# Power_Cape.net
KiCad netlist of a schematic drawn in EAGLE
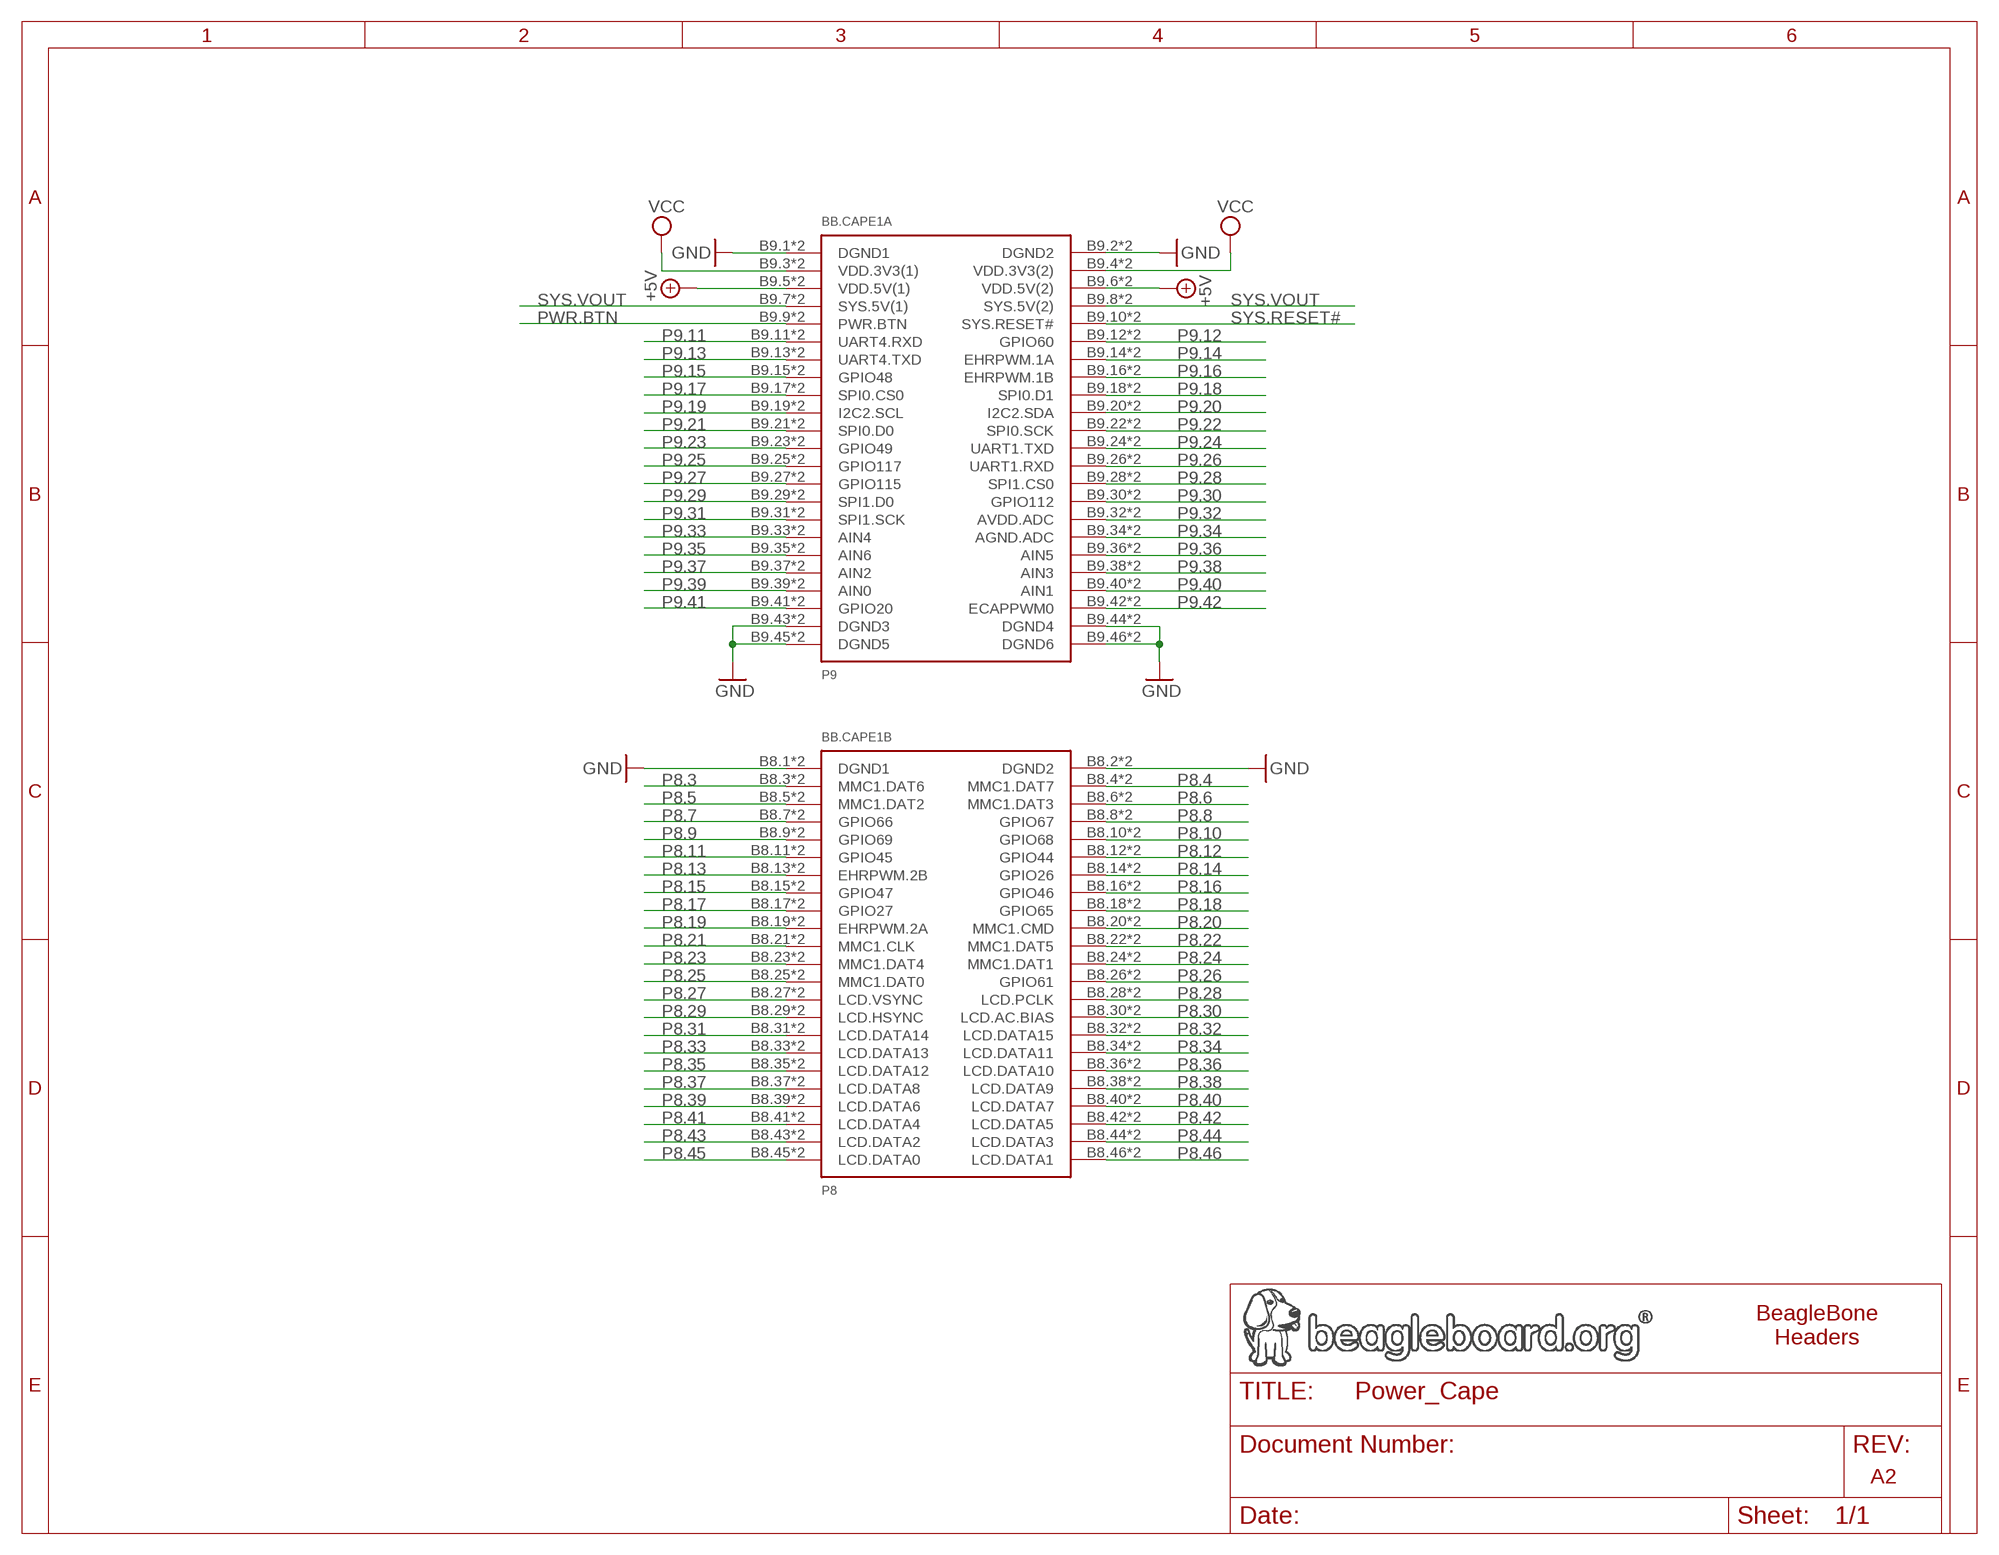
[diagram p0: schematic, sheet 1, part 1 of 2]
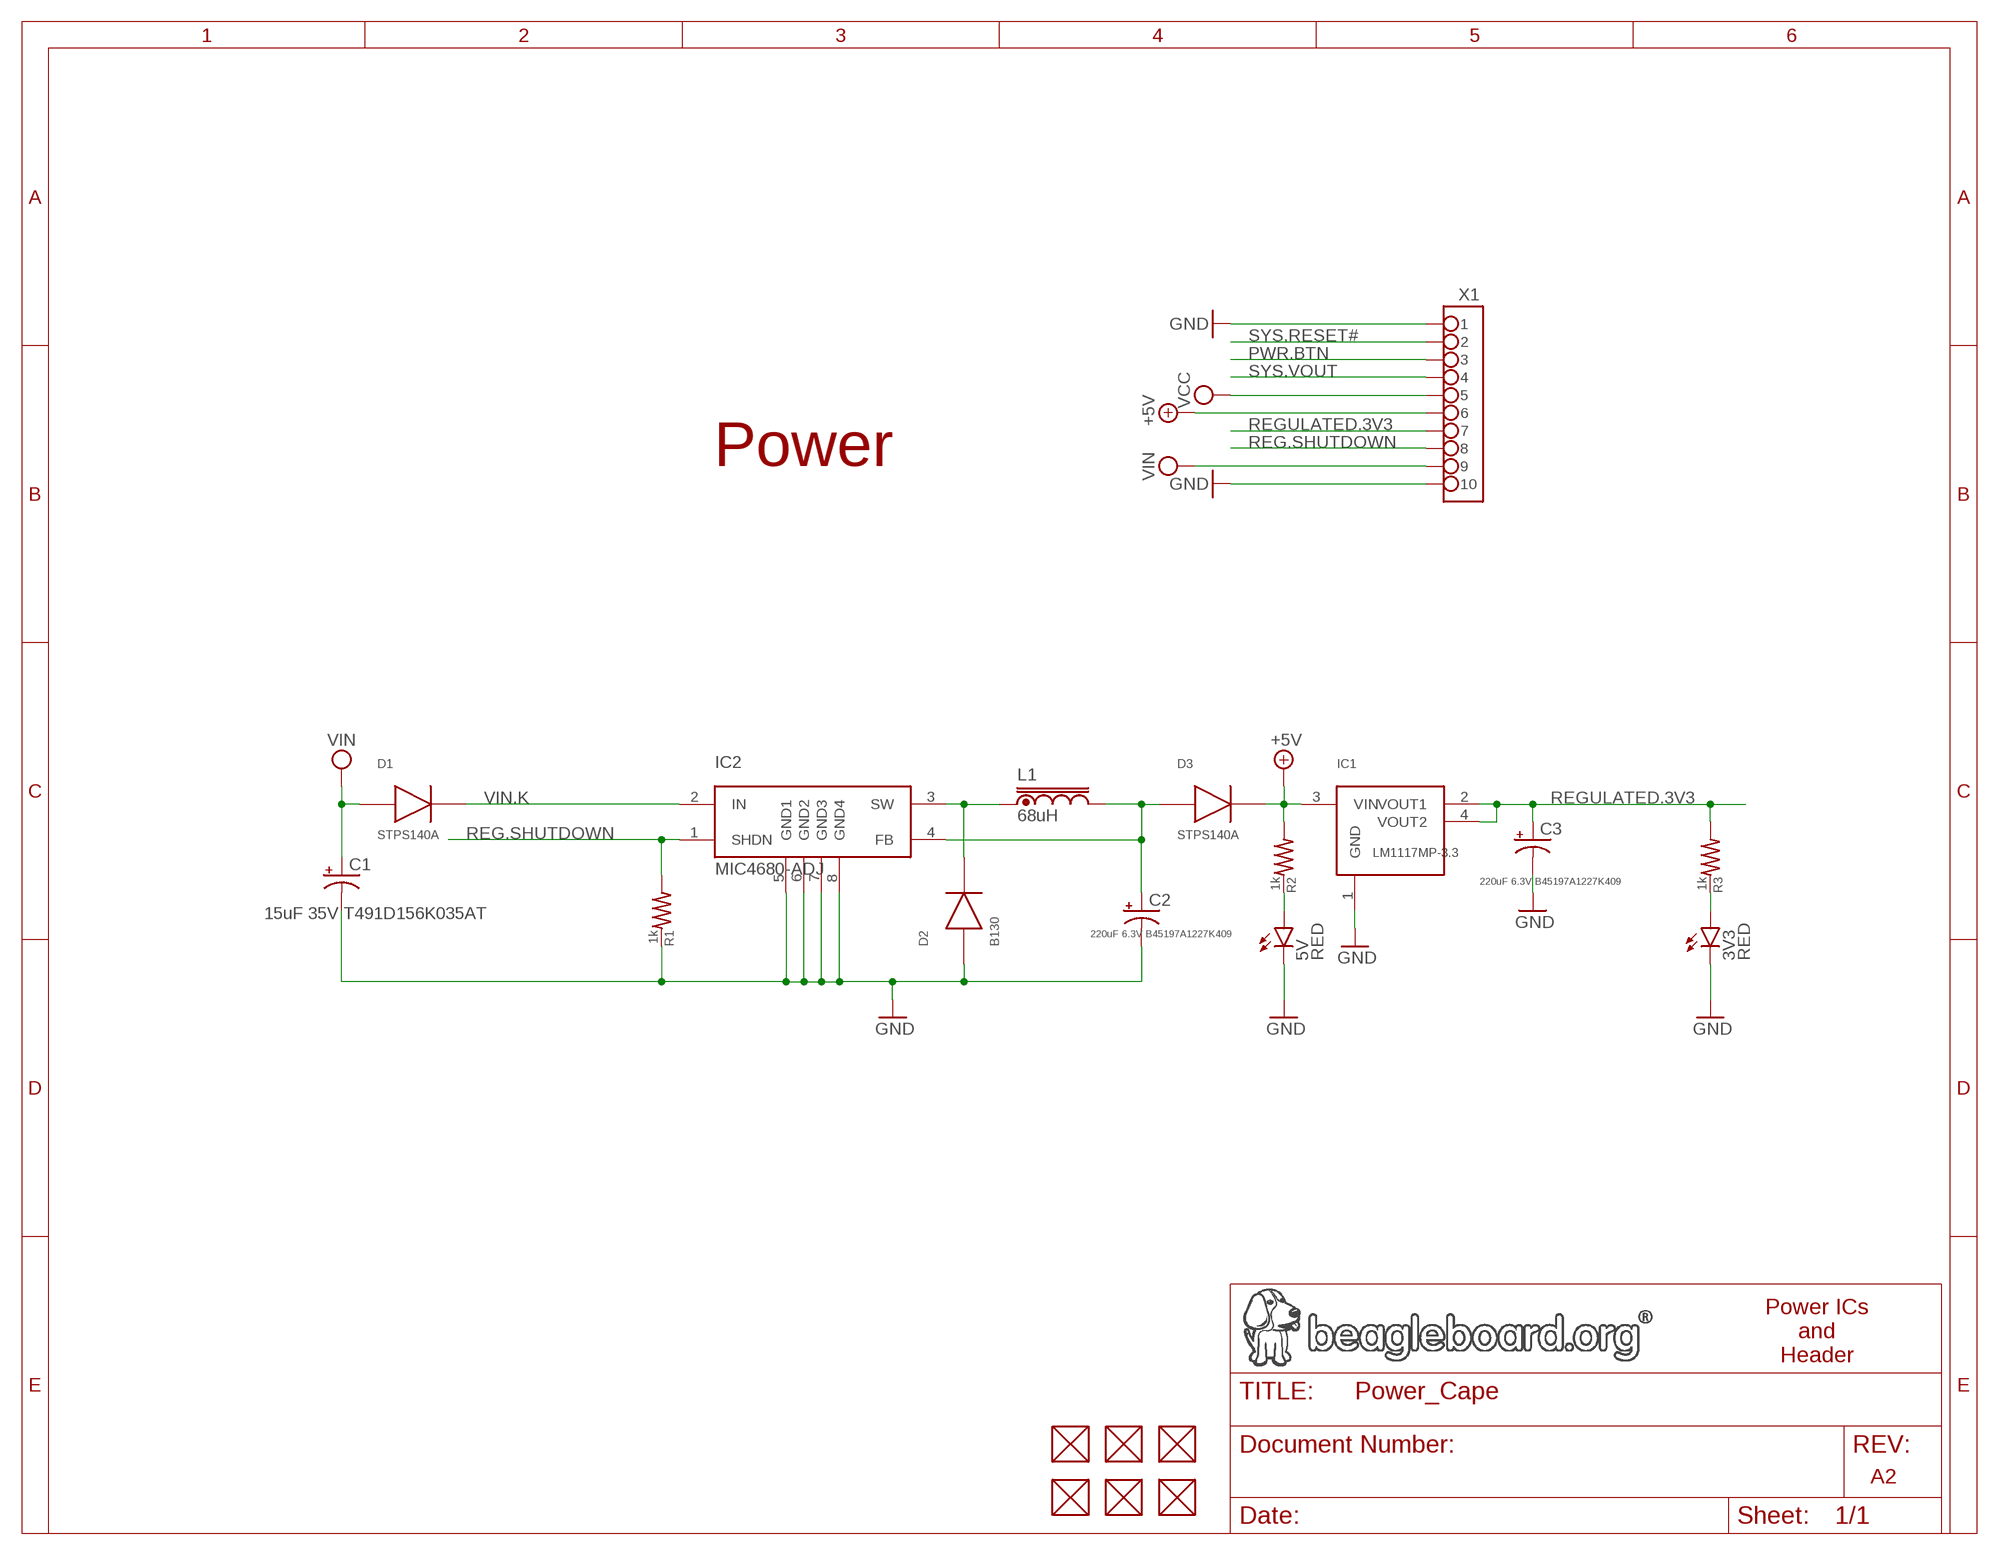
[diagram p1: schematic, sheet 1, part 2 of 2]

(export (version "E")
  (design (tool "Eeschema 10.0.6"))
  (components
    (comp (ref "3V3")
      (value "RED")
      (footprint "eagle-import:0805-LED")
      (libsource (lib "eagle-import") (part "LED-(INCH)-0805"))
    )
    (comp (ref "5V")
      (value "RED")
      (footprint "eagle-import:0805-LED")
      (libsource (lib "eagle-import") (part "LED-(INCH)-0805"))
    )
    (comp (ref "BB.CAPE1")
      (value "BEAGLEBONE.CAPE.TOP/BOTTOM-PADS")
      (footprint "eagle-import:BEAGLEBONE.CAPE.TOP_BOTTOM-PADS")
      (libsource (lib "eagle-import") (part "BEAGLEBONE.CAPE.TOP/BOTTOM-PADS"))
    )
    (comp (ref "C1")
      (value "15uF 35V T491D156K035AT")
      (footprint "eagle-import:D_7343-31W")
      (libsource (lib "eagle-import") (part "CPOL-USD/7343-31W"))
    )
    (comp (ref "C2")
      (value "220uF 6.3V B45197A1227K409")
      (footprint "eagle-import:D_7343-31W")
      (libsource (lib "eagle-import") (part "CPOL-USD/7343-31W"))
    )
    (comp (ref "C3")
      (value "220uF 6.3V B45197A1227K409")
      (footprint "eagle-import:D_7343-31W")
      (libsource (lib "eagle-import") (part "CPOL-USD/7343-31W"))
    )
    (comp (ref "D1")
      (value "STPS140A")
      (footprint "eagle-import:DIODE_SMA")
      (libsource (lib "eagle-import") (part "DIODE_SMA"))
    )
    (comp (ref "D2")
      (value "B130")
      (footprint "eagle-import:DIODE_SMA")
      (libsource (lib "eagle-import") (part "DIODE_SMA"))
    )
    (comp (ref "D3")
      (value "STPS140A")
      (footprint "eagle-import:DIODE_SMA")
      (libsource (lib "eagle-import") (part "DIODE_SMA"))
    )
    (comp (ref "FUD1")
      (value "FIDUCIAL")
      (footprint "eagle-import:FIDUCIAL_40MIL")
      (libsource (lib "eagle-import") (part "FIDUCIAL"))
    )
    (comp (ref "FUD2")
      (value "FIDUCIAL")
      (footprint "eagle-import:FIDUCIAL_40MIL")
      (libsource (lib "eagle-import") (part "FIDUCIAL"))
    )
    (comp (ref "FUD3")
      (value "FIDUCIAL")
      (footprint "eagle-import:FIDUCIAL_40MIL")
      (libsource (lib "eagle-import") (part "FIDUCIAL"))
    )
    (comp (ref "FUD4")
      (value "FIDUCIAL")
      (footprint "eagle-import:FIDUCIAL_40MIL")
      (libsource (lib "eagle-import") (part "FIDUCIAL"))
    )
    (comp (ref "FUD5")
      (value "FIDUCIAL")
      (footprint "eagle-import:FIDUCIAL_40MIL")
      (libsource (lib "eagle-import") (part "FIDUCIAL"))
    )
    (comp (ref "FUD6")
      (value "FIDUCIAL")
      (footprint "eagle-import:FIDUCIAL_40MIL")
      (libsource (lib "eagle-import") (part "FIDUCIAL"))
    )
    (comp (ref "IC1")
      (value "LM1117MP-3.3")
      (footprint "eagle-import:SOT223")
      (libsource (lib "eagle-import") (part "LM1117"))
    )
    (comp (ref "IC2")
      (value "MIC4680-ADJ")
      (footprint "eagle-import:SO8")
      (libsource (lib "eagle-import") (part "MIC4680"))
    )
    (comp (ref "L1")
      (value "68uH")
      (footprint "eagle-import:UP2B-(UNI-PAC)")
      (libsource (lib "eagle-import") (part "UP2B-XXX"))
    )
    (comp (ref "R1")
      (value "1k")
      (footprint "eagle-import:0402")
      (libsource (lib "eagle-import") (part "RESISTOR-(INCH)-0402"))
    )
    (comp (ref "R2")
      (value "1k")
      (footprint "eagle-import:0402")
      (libsource (lib "eagle-import") (part "RESISTOR-(INCH)-0402"))
    )
    (comp (ref "R3")
      (value "1k")
      (footprint "eagle-import:0402")
      (libsource (lib "eagle-import") (part "RESISTOR-(INCH)-0402"))
    )
    (comp (ref "X1")
      (value "TB-10TERM-150MIL.PITCH")
      (footprint "eagle-import:TERMINAL.BLOCK-10TERM-150MIL.PITCH")
      (libsource (lib "eagle-import") (part "TB-10TERM-150MIL.PITCH"))
    )
  )
  (nets
    (net (code "1") (name "+5V") (class "Default")
      (node (ref "BB.CAPE1") (pin "B9.5") (pinfunction "VDD.5V(1)_B9.5") (pintype "bidirectional"))
      (node (ref "BB.CAPE1") (pin "B9.6") (pinfunction "VDD.5V(2)_B9.6") (pintype "bidirectional"))
      (node (ref "BB.CAPE1") (pin "T9.5") (pinfunction "VDD.5V(1)_T9.5") (pintype "bidirectional"))
      (node (ref "BB.CAPE1") (pin "T9.6") (pinfunction "VDD.5V(2)_T9.6") (pintype "bidirectional"))
      (node (ref "D3") (pin "K") (pinfunction "K_K") (pintype "bidirectional"))
      (node (ref "IC1") (pin "3") (pinfunction "VIN_3") (pintype "bidirectional"))
      (node (ref "R2") (pin "1") (pinfunction "1_1") (pintype "bidirectional"))
      (node (ref "X1") (pin "6") (pinfunction "6_6") (pintype "bidirectional"))
    )
    (net (code "2") (name "/P8.3") (class "Default")
      (node (ref "BB.CAPE1") (pin "B8.3") (pinfunction "MMC1.DAT6_B8.3") (pintype "bidirectional"))
      (node (ref "BB.CAPE1") (pin "T8.3") (pinfunction "MMC1.DAT6_T8.3") (pintype "bidirectional"))
    )
    (net (code "3") (name "/P8.4") (class "Default")
      (node (ref "BB.CAPE1") (pin "B8.4") (pinfunction "MMC1.DAT7_B8.4") (pintype "bidirectional"))
      (node (ref "BB.CAPE1") (pin "T8.4") (pinfunction "MMC1.DAT7_T8.4") (pintype "bidirectional"))
    )
    (net (code "4") (name "/P8.5") (class "Default")
      (node (ref "BB.CAPE1") (pin "B8.5") (pinfunction "MMC1.DAT2_B8.5") (pintype "bidirectional"))
      (node (ref "BB.CAPE1") (pin "T8.5") (pinfunction "MMC1.DAT2_T8.5") (pintype "bidirectional"))
    )
    (net (code "5") (name "/P8.6") (class "Default")
      (node (ref "BB.CAPE1") (pin "B8.6") (pinfunction "MMC1.DAT3_B8.6") (pintype "bidirectional"))
      (node (ref "BB.CAPE1") (pin "T8.6") (pinfunction "MMC1.DAT3_T8.6") (pintype "bidirectional"))
    )
    (net (code "6") (name "/P8.7") (class "Default")
      (node (ref "BB.CAPE1") (pin "B8.7") (pinfunction "GPIO66_B8.7") (pintype "bidirectional"))
      (node (ref "BB.CAPE1") (pin "T8.7") (pinfunction "GPIO66_T8.7") (pintype "bidirectional"))
    )
    (net (code "7") (name "/P8.8") (class "Default")
      (node (ref "BB.CAPE1") (pin "B8.8") (pinfunction "GPIO67_B8.8") (pintype "bidirectional"))
      (node (ref "BB.CAPE1") (pin "T8.8") (pinfunction "GPIO67_T8.8") (pintype "bidirectional"))
    )
    (net (code "8") (name "/P8.9") (class "Default")
      (node (ref "BB.CAPE1") (pin "B8.9") (pinfunction "GPIO69_B8.9") (pintype "bidirectional"))
      (node (ref "BB.CAPE1") (pin "T8.9") (pinfunction "GPIO69_T8.9") (pintype "bidirectional"))
    )
    (net (code "9") (name "/P8.10") (class "Default")
      (node (ref "BB.CAPE1") (pin "B8.10") (pinfunction "GPIO68_B8.10") (pintype "bidirectional"))
      (node (ref "BB.CAPE1") (pin "T8.10") (pinfunction "GPIO68_T8.10") (pintype "bidirectional"))
    )
    (net (code "10") (name "/P8.11") (class "Default")
      (node (ref "BB.CAPE1") (pin "B8.11") (pinfunction "GPIO45_B8.11") (pintype "bidirectional"))
      (node (ref "BB.CAPE1") (pin "T8.11") (pinfunction "GPIO45_T8.11") (pintype "bidirectional"))
    )
    (net (code "11") (name "/P8.12") (class "Default")
      (node (ref "BB.CAPE1") (pin "B8.12") (pinfunction "GPIO44_B8.12") (pintype "bidirectional"))
      (node (ref "BB.CAPE1") (pin "T8.12") (pinfunction "GPIO44_T8.12") (pintype "bidirectional"))
    )
    (net (code "12") (name "/P8.13") (class "Default")
      (node (ref "BB.CAPE1") (pin "B8.13") (pinfunction "EHRPWM.2B_B8.13") (pintype "bidirectional"))
      (node (ref "BB.CAPE1") (pin "T8.13") (pinfunction "EHRPWM.2B_T8.13") (pintype "bidirectional"))
    )
    (net (code "13") (name "/P8.14") (class "Default")
      (node (ref "BB.CAPE1") (pin "B8.14") (pinfunction "GPIO26_B8.14") (pintype "bidirectional"))
      (node (ref "BB.CAPE1") (pin "T8.14") (pinfunction "GPIO26_T8.14") (pintype "bidirectional"))
    )
    (net (code "14") (name "/P8.15") (class "Default")
      (node (ref "BB.CAPE1") (pin "B8.15") (pinfunction "GPIO47_B8.15") (pintype "bidirectional"))
      (node (ref "BB.CAPE1") (pin "T8.15") (pinfunction "GPIO47_T8.15") (pintype "bidirectional"))
    )
    (net (code "15") (name "/P8.16") (class "Default")
      (node (ref "BB.CAPE1") (pin "B8.16") (pinfunction "GPIO46_B8.16") (pintype "bidirectional"))
      (node (ref "BB.CAPE1") (pin "T8.16") (pinfunction "GPIO46_T8.16") (pintype "bidirectional"))
    )
    (net (code "16") (name "/P8.17") (class "Default")
      (node (ref "BB.CAPE1") (pin "B8.17") (pinfunction "GPIO27_B8.17") (pintype "bidirectional"))
      (node (ref "BB.CAPE1") (pin "T8.17") (pinfunction "GPIO27_T8.17") (pintype "bidirectional"))
    )
    (net (code "17") (name "/P8.18") (class "Default")
      (node (ref "BB.CAPE1") (pin "B8.18") (pinfunction "GPIO65_B8.18") (pintype "bidirectional"))
      (node (ref "BB.CAPE1") (pin "T8.18") (pinfunction "GPIO65_T8.18") (pintype "bidirectional"))
    )
    (net (code "18") (name "/P8.19") (class "Default")
      (node (ref "BB.CAPE1") (pin "B8.19") (pinfunction "EHRPWM.2A_B8.19") (pintype "bidirectional"))
      (node (ref "BB.CAPE1") (pin "T8.19") (pinfunction "EHRPWM.2A_T8.19") (pintype "bidirectional"))
    )
    (net (code "19") (name "/P8.20") (class "Default")
      (node (ref "BB.CAPE1") (pin "B8.20") (pinfunction "MMC1.CMD_B8.20") (pintype "bidirectional"))
      (node (ref "BB.CAPE1") (pin "T8.20") (pinfunction "MMC1.CMD_T8.20") (pintype "bidirectional"))
    )
    (net (code "20") (name "/P8.21") (class "Default")
      (node (ref "BB.CAPE1") (pin "B8.21") (pinfunction "MMC1.CLK_B8.21") (pintype "bidirectional"))
      (node (ref "BB.CAPE1") (pin "T8.21") (pinfunction "MMC1.CLK_T8.21") (pintype "bidirectional"))
    )
    (net (code "21") (name "/P8.22") (class "Default")
      (node (ref "BB.CAPE1") (pin "B8.22") (pinfunction "MMC1.DAT5_B8.22") (pintype "bidirectional"))
      (node (ref "BB.CAPE1") (pin "T8.22") (pinfunction "MMC1.DAT5_T8.22") (pintype "bidirectional"))
    )
    (net (code "22") (name "/P8.23") (class "Default")
      (node (ref "BB.CAPE1") (pin "B8.23") (pinfunction "MMC1.DAT4_B8.23") (pintype "bidirectional"))
      (node (ref "BB.CAPE1") (pin "T8.23") (pinfunction "MMC1.DAT4_T8.23") (pintype "bidirectional"))
    )
    (net (code "23") (name "/P8.24") (class "Default")
      (node (ref "BB.CAPE1") (pin "B8.24") (pinfunction "MMC1.DAT1_B8.24") (pintype "bidirectional"))
      (node (ref "BB.CAPE1") (pin "T8.24") (pinfunction "MMC1.DAT1_T8.24") (pintype "bidirectional"))
    )
    (net (code "24") (name "/P8.25") (class "Default")
      (node (ref "BB.CAPE1") (pin "B8.25") (pinfunction "MMC1.DAT0_B8.25") (pintype "bidirectional"))
      (node (ref "BB.CAPE1") (pin "T8.25") (pinfunction "MMC1.DAT0_T8.25") (pintype "bidirectional"))
    )
    (net (code "25") (name "/P8.26") (class "Default")
      (node (ref "BB.CAPE1") (pin "B8.26") (pinfunction "GPIO61_B8.26") (pintype "bidirectional"))
      (node (ref "BB.CAPE1") (pin "T8.26") (pinfunction "GPIO61_T8.26") (pintype "bidirectional"))
    )
    (net (code "26") (name "/P8.27") (class "Default")
      (node (ref "BB.CAPE1") (pin "B8.27") (pinfunction "LCD.VSYNC_B8.27") (pintype "bidirectional"))
      (node (ref "BB.CAPE1") (pin "T8.27") (pinfunction "LCD.VSYNC_T8.27") (pintype "bidirectional"))
    )
    (net (code "27") (name "/P8.28") (class "Default")
      (node (ref "BB.CAPE1") (pin "B8.28") (pinfunction "LCD.PCLK_B8.28") (pintype "bidirectional"))
      (node (ref "BB.CAPE1") (pin "T8.28") (pinfunction "LCD.PCLK_T8.28") (pintype "bidirectional"))
    )
    (net (code "28") (name "/P8.29") (class "Default")
      (node (ref "BB.CAPE1") (pin "B8.29") (pinfunction "LCD.HSYNC_B8.29") (pintype "bidirectional"))
      (node (ref "BB.CAPE1") (pin "T8.29") (pinfunction "LCD.HSYNC_T8.29") (pintype "bidirectional"))
    )
    (net (code "29") (name "/P8.30") (class "Default")
      (node (ref "BB.CAPE1") (pin "B8.30") (pinfunction "LCD.AC.BIAS_B8.30") (pintype "bidirectional"))
      (node (ref "BB.CAPE1") (pin "T8.30") (pinfunction "LCD.AC.BIAS_T8.30") (pintype "bidirectional"))
    )
    (net (code "30") (name "/P8.31") (class "Default")
      (node (ref "BB.CAPE1") (pin "B8.31") (pinfunction "LCD.DATA14_B8.31") (pintype "bidirectional"))
      (node (ref "BB.CAPE1") (pin "T8.31") (pinfunction "LCD.DATA14_T8.31") (pintype "bidirectional"))
    )
    (net (code "31") (name "/P8.32") (class "Default")
      (node (ref "BB.CAPE1") (pin "B8.32") (pinfunction "LCD.DATA15_B8.32") (pintype "bidirectional"))
      (node (ref "BB.CAPE1") (pin "T8.32") (pinfunction "LCD.DATA15_T8.32") (pintype "bidirectional"))
    )
    (net (code "32") (name "/P8.33") (class "Default")
      (node (ref "BB.CAPE1") (pin "B8.33") (pinfunction "LCD.DATA13_B8.33") (pintype "bidirectional"))
      (node (ref "BB.CAPE1") (pin "T8.33") (pinfunction "LCD.DATA13_T8.33") (pintype "bidirectional"))
    )
    (net (code "33") (name "/P8.34") (class "Default")
      (node (ref "BB.CAPE1") (pin "B8.34") (pinfunction "LCD.DATA11_B8.34") (pintype "bidirectional"))
      (node (ref "BB.CAPE1") (pin "T8.34") (pinfunction "LCD.DATA11_T8.34") (pintype "bidirectional"))
    )
    (net (code "34") (name "/P8.35") (class "Default")
      (node (ref "BB.CAPE1") (pin "B8.35") (pinfunction "LCD.DATA12_B8.35") (pintype "bidirectional"))
      (node (ref "BB.CAPE1") (pin "T8.35") (pinfunction "LCD.DATA12_T8.35") (pintype "bidirectional"))
    )
    (net (code "35") (name "/P8.36") (class "Default")
      (node (ref "BB.CAPE1") (pin "B8.36") (pinfunction "LCD.DATA10_B8.36") (pintype "bidirectional"))
      (node (ref "BB.CAPE1") (pin "T8.36") (pinfunction "LCD.DATA10_T8.36") (pintype "bidirectional"))
    )
    (net (code "36") (name "/P8.37") (class "Default")
      (node (ref "BB.CAPE1") (pin "B8.37") (pinfunction "LCD.DATA8_B8.37") (pintype "bidirectional"))
      (node (ref "BB.CAPE1") (pin "T8.37") (pinfunction "LCD.DATA8_T8.37") (pintype "bidirectional"))
    )
    (net (code "37") (name "/P8.38") (class "Default")
      (node (ref "BB.CAPE1") (pin "B8.38") (pinfunction "LCD.DATA9_B8.38") (pintype "bidirectional"))
      (node (ref "BB.CAPE1") (pin "T8.38") (pinfunction "LCD.DATA9_T8.38") (pintype "bidirectional"))
    )
    (net (code "38") (name "/P8.39") (class "Default")
      (node (ref "BB.CAPE1") (pin "B8.39") (pinfunction "LCD.DATA6_B8.39") (pintype "bidirectional"))
      (node (ref "BB.CAPE1") (pin "T8.39") (pinfunction "LCD.DATA6_T8.39") (pintype "bidirectional"))
    )
    (net (code "39") (name "/P8.40") (class "Default")
      (node (ref "BB.CAPE1") (pin "B8.40") (pinfunction "LCD.DATA7_B8.40") (pintype "bidirectional"))
      (node (ref "BB.CAPE1") (pin "T8.40") (pinfunction "LCD.DATA7_T8.40") (pintype "bidirectional"))
    )
    (net (code "40") (name "/P8.41") (class "Default")
      (node (ref "BB.CAPE1") (pin "B8.41") (pinfunction "LCD.DATA4_B8.41") (pintype "bidirectional"))
      (node (ref "BB.CAPE1") (pin "T8.41") (pinfunction "LCD.DATA4_T8.41") (pintype "bidirectional"))
    )
    (net (code "41") (name "/P8.42") (class "Default")
      (node (ref "BB.CAPE1") (pin "B8.42") (pinfunction "LCD.DATA5_B8.42") (pintype "bidirectional"))
      (node (ref "BB.CAPE1") (pin "T8.42") (pinfunction "LCD.DATA5_T8.42") (pintype "bidirectional"))
    )
    (net (code "42") (name "/P8.43") (class "Default")
      (node (ref "BB.CAPE1") (pin "B8.43") (pinfunction "LCD.DATA2_B8.43") (pintype "bidirectional"))
      (node (ref "BB.CAPE1") (pin "T8.43") (pinfunction "LCD.DATA2_T8.43") (pintype "bidirectional"))
    )
    (net (code "43") (name "/P8.44") (class "Default")
      (node (ref "BB.CAPE1") (pin "B8.44") (pinfunction "LCD.DATA3_B8.44") (pintype "bidirectional"))
      (node (ref "BB.CAPE1") (pin "T8.44") (pinfunction "LCD.DATA3_T8.44") (pintype "bidirectional"))
    )
    (net (code "44") (name "/P8.45") (class "Default")
      (node (ref "BB.CAPE1") (pin "B8.45") (pinfunction "LCD.DATA0_B8.45") (pintype "bidirectional"))
      (node (ref "BB.CAPE1") (pin "T8.45") (pinfunction "LCD.DATA0_T8.45") (pintype "bidirectional"))
    )
    (net (code "45") (name "/P8.46") (class "Default")
      (node (ref "BB.CAPE1") (pin "B8.46") (pinfunction "LCD.DATA1_B8.46") (pintype "bidirectional"))
      (node (ref "BB.CAPE1") (pin "T8.46") (pinfunction "LCD.DATA1_T8.46") (pintype "bidirectional"))
    )
    (net (code "46") (name "/P9.11") (class "Default")
      (node (ref "BB.CAPE1") (pin "B9.11") (pinfunction "UART4.RXD_B9.11") (pintype "bidirectional"))
      (node (ref "BB.CAPE1") (pin "T9.11") (pinfunction "UART4.RXD_T9.11") (pintype "bidirectional"))
    )
    (net (code "47") (name "/P9.12") (class "Default")
      (node (ref "BB.CAPE1") (pin "B9.12") (pinfunction "GPIO60_B9.12") (pintype "bidirectional"))
      (node (ref "BB.CAPE1") (pin "T9.12") (pinfunction "GPIO60_T9.12") (pintype "bidirectional"))
    )
    (net (code "48") (name "/P9.13") (class "Default")
      (node (ref "BB.CAPE1") (pin "B9.13") (pinfunction "UART4.TXD_B9.13") (pintype "bidirectional"))
      (node (ref "BB.CAPE1") (pin "T9.13") (pinfunction "UART4.TXD_T9.13") (pintype "bidirectional"))
    )
    (net (code "49") (name "/P9.14") (class "Default")
      (node (ref "BB.CAPE1") (pin "B9.14") (pinfunction "EHRPWM.1A_B9.14") (pintype "bidirectional"))
      (node (ref "BB.CAPE1") (pin "T9.14") (pinfunction "EHRPWM.1A_T9.14") (pintype "bidirectional"))
    )
    (net (code "50") (name "/P9.15") (class "Default")
      (node (ref "BB.CAPE1") (pin "B9.15") (pinfunction "GPIO48_B9.15") (pintype "bidirectional"))
      (node (ref "BB.CAPE1") (pin "T9.15") (pinfunction "GPIO48_T9.15") (pintype "bidirectional"))
    )
    (net (code "51") (name "/P9.16") (class "Default")
      (node (ref "BB.CAPE1") (pin "B9.16") (pinfunction "EHRPWM.1B_B9.16") (pintype "bidirectional"))
      (node (ref "BB.CAPE1") (pin "T9.16") (pinfunction "EHRPWM.1B_T9.16") (pintype "bidirectional"))
    )
    (net (code "52") (name "/P9.17") (class "Default")
      (node (ref "BB.CAPE1") (pin "B9.17") (pinfunction "SPI0.CS0_B9.17") (pintype "bidirectional"))
      (node (ref "BB.CAPE1") (pin "T9.17") (pinfunction "SPI0.CS0_T9.17") (pintype "bidirectional"))
    )
    (net (code "53") (name "/P9.18") (class "Default")
      (node (ref "BB.CAPE1") (pin "B9.18") (pinfunction "SPI0.D1_B9.18") (pintype "bidirectional"))
      (node (ref "BB.CAPE1") (pin "T9.18") (pinfunction "SPI0.D1_T9.18") (pintype "bidirectional"))
    )
    (net (code "54") (name "/P9.19") (class "Default")
      (node (ref "BB.CAPE1") (pin "B9.19") (pinfunction "I2C2.SCL_B9.19") (pintype "bidirectional"))
      (node (ref "BB.CAPE1") (pin "T9.19") (pinfunction "I2C2.SCL_T9.19") (pintype "bidirectional"))
    )
    (net (code "55") (name "/P9.20") (class "Default")
      (node (ref "BB.CAPE1") (pin "B9.20") (pinfunction "I2C2.SDA_B9.20") (pintype "bidirectional"))
      (node (ref "BB.CAPE1") (pin "T9.20") (pinfunction "I2C2.SDA_T9.20") (pintype "bidirectional"))
    )
    (net (code "56") (name "/P9.21") (class "Default")
      (node (ref "BB.CAPE1") (pin "B9.21") (pinfunction "SPI0.D0_B9.21") (pintype "bidirectional"))
      (node (ref "BB.CAPE1") (pin "T9.21") (pinfunction "SPI0.D0_T9.21") (pintype "bidirectional"))
    )
    (net (code "57") (name "/P9.22") (class "Default")
      (node (ref "BB.CAPE1") (pin "B9.22") (pinfunction "SPI0.SCK_B9.22") (pintype "bidirectional"))
      (node (ref "BB.CAPE1") (pin "T9.22") (pinfunction "SPI0.SCK_T9.22") (pintype "bidirectional"))
    )
    (net (code "58") (name "/P9.23") (class "Default")
      (node (ref "BB.CAPE1") (pin "B9.23") (pinfunction "GPIO49_B9.23") (pintype "bidirectional"))
      (node (ref "BB.CAPE1") (pin "T9.23") (pinfunction "GPIO49_T9.23") (pintype "bidirectional"))
    )
    (net (code "59") (name "/P9.24") (class "Default")
      (node (ref "BB.CAPE1") (pin "B9.24") (pinfunction "UART1.TXD_B9.24") (pintype "bidirectional"))
      (node (ref "BB.CAPE1") (pin "T9.24") (pinfunction "UART1.TXD_T9.24") (pintype "bidirectional"))
    )
    (net (code "60") (name "/P9.25") (class "Default")
      (node (ref "BB.CAPE1") (pin "B9.25") (pinfunction "GPIO117_B9.25") (pintype "bidirectional"))
      (node (ref "BB.CAPE1") (pin "T9.25") (pinfunction "GPIO117_T9.25") (pintype "bidirectional"))
    )
    (net (code "61") (name "/P9.26") (class "Default")
      (node (ref "BB.CAPE1") (pin "B9.26") (pinfunction "UART1.RXD_B9.26") (pintype "bidirectional"))
      (node (ref "BB.CAPE1") (pin "T9.26") (pinfunction "UART1.RXD_T9.26") (pintype "bidirectional"))
    )
    (net (code "62") (name "/P9.27") (class "Default")
      (node (ref "BB.CAPE1") (pin "B9.27") (pinfunction "GPIO115_B9.27") (pintype "bidirectional"))
      (node (ref "BB.CAPE1") (pin "T9.27") (pinfunction "GPIO115_T9.27") (pintype "bidirectional"))
    )
    (net (code "63") (name "/P9.28") (class "Default")
      (node (ref "BB.CAPE1") (pin "B9.28") (pinfunction "SPI1.CS0_B9.28") (pintype "bidirectional"))
      (node (ref "BB.CAPE1") (pin "T9.28") (pinfunction "SPI1.CS0_T9.28") (pintype "bidirectional"))
    )
    (net (code "64") (name "/P9.29") (class "Default")
      (node (ref "BB.CAPE1") (pin "B9.29") (pinfunction "SPI1.D0_B9.29") (pintype "bidirectional"))
      (node (ref "BB.CAPE1") (pin "T9.29") (pinfunction "SPI1.D0_T9.29") (pintype "bidirectional"))
    )
    (net (code "65") (name "/P9.30") (class "Default")
      (node (ref "BB.CAPE1") (pin "B9.30") (pinfunction "GPIO112_B9.30") (pintype "bidirectional"))
      (node (ref "BB.CAPE1") (pin "T9.30") (pinfunction "GPIO112_T9.30") (pintype "bidirectional"))
    )
    (net (code "66") (name "/P9.31") (class "Default")
      (node (ref "BB.CAPE1") (pin "B9.31") (pinfunction "SPI1.SCK_B9.31") (pintype "bidirectional"))
      (node (ref "BB.CAPE1") (pin "T9.31") (pinfunction "SPI1.SCK_T9.31") (pintype "bidirectional"))
    )
    (net (code "67") (name "/P9.32") (class "Default")
      (node (ref "BB.CAPE1") (pin "B9.32") (pinfunction "AVDD.ADC_B9.32") (pintype "bidirectional"))
      (node (ref "BB.CAPE1") (pin "T9.32") (pinfunction "AVDD.ADC_T9.32") (pintype "bidirectional"))
    )
    (net (code "68") (name "/P9.33") (class "Default")
      (node (ref "BB.CAPE1") (pin "B9.33") (pinfunction "AIN4_B9.33") (pintype "bidirectional"))
      (node (ref "BB.CAPE1") (pin "T9.33") (pinfunction "AIN4_T9.33") (pintype "bidirectional"))
    )
    (net (code "69") (name "/P9.34") (class "Default")
      (node (ref "BB.CAPE1") (pin "B9.34") (pinfunction "AGND.ADC_B9.34") (pintype "bidirectional"))
      (node (ref "BB.CAPE1") (pin "T9.34") (pinfunction "AGND.ADC_T9.34") (pintype "bidirectional"))
    )
    (net (code "70") (name "/P9.35") (class "Default")
      (node (ref "BB.CAPE1") (pin "B9.35") (pinfunction "AIN6_B9.35") (pintype "bidirectional"))
      (node (ref "BB.CAPE1") (pin "T9.35") (pinfunction "AIN6_T9.35") (pintype "bidirectional"))
    )
    (net (code "71") (name "/P9.36") (class "Default")
      (node (ref "BB.CAPE1") (pin "B9.36") (pinfunction "AIN5_B9.36") (pintype "bidirectional"))
      (node (ref "BB.CAPE1") (pin "T9.36") (pinfunction "AIN5_T9.36") (pintype "bidirectional"))
    )
    (net (code "72") (name "/P9.37") (class "Default")
      (node (ref "BB.CAPE1") (pin "B9.37") (pinfunction "AIN2_B9.37") (pintype "bidirectional"))
      (node (ref "BB.CAPE1") (pin "T9.37") (pinfunction "AIN2_T9.37") (pintype "bidirectional"))
    )
    (net (code "73") (name "/P9.38") (class "Default")
      (node (ref "BB.CAPE1") (pin "B9.38") (pinfunction "AIN3_B9.38") (pintype "bidirectional"))
      (node (ref "BB.CAPE1") (pin "T9.38") (pinfunction "AIN3_T9.38") (pintype "bidirectional"))
    )
    (net (code "74") (name "/P9.39") (class "Default")
      (node (ref "BB.CAPE1") (pin "B9.39") (pinfunction "AIN0_B9.39") (pintype "bidirectional"))
      (node (ref "BB.CAPE1") (pin "T9.39") (pinfunction "AIN0_T9.39") (pintype "bidirectional"))
    )
    (net (code "75") (name "/P9.40") (class "Default")
      (node (ref "BB.CAPE1") (pin "B9.40") (pinfunction "AIN1_B9.40") (pintype "bidirectional"))
      (node (ref "BB.CAPE1") (pin "T9.40") (pinfunction "AIN1_T9.40") (pintype "bidirectional"))
    )
    (net (code "76") (name "/P9.41") (class "Default")
      (node (ref "BB.CAPE1") (pin "B9.41") (pinfunction "GPIO20_B9.41") (pintype "bidirectional"))
      (node (ref "BB.CAPE1") (pin "T9.41") (pinfunction "GPIO20_T9.41") (pintype "bidirectional"))
    )
    (net (code "77") (name "/P9.42") (class "Default")
      (node (ref "BB.CAPE1") (pin "B9.42") (pinfunction "ECAPPWM0_B9.42") (pintype "bidirectional"))
      (node (ref "BB.CAPE1") (pin "T9.42") (pinfunction "ECAPPWM0_T9.42") (pintype "bidirectional"))
    )
    (net (code "78") (name "/PWR.BTN") (class "Default")
      (node (ref "BB.CAPE1") (pin "B9.9") (pinfunction "PWR.BTN_B9.9") (pintype "bidirectional"))
      (node (ref "BB.CAPE1") (pin "T9.9") (pinfunction "PWR.BTN_T9.9") (pintype "bidirectional"))
      (node (ref "X1") (pin "3") (pinfunction "3_3") (pintype "bidirectional"))
    )
    (net (code "79") (name "/REG.SHUTDOWN") (class "Default")
      (node (ref "IC2") (pin "1") (pinfunction "SHDN_1") (pintype "bidirectional"))
      (node (ref "R1") (pin "1") (pinfunction "1_1") (pintype "bidirectional"))
      (node (ref "X1") (pin "8") (pinfunction "8_8") (pintype "bidirectional"))
    )
    (net (code "80") (name "/REGULATED.3V3") (class "Default")
      (node (ref "C3") (pin "+") (pinfunction "+_+") (pintype "passive"))
      (node (ref "IC1") (pin "2") (pinfunction "VOUT1_2") (pintype "bidirectional"))
      (node (ref "IC1") (pin "4") (pinfunction "VOUT2_4") (pintype "bidirectional"))
      (node (ref "R3") (pin "1") (pinfunction "1_1") (pintype "bidirectional"))
      (node (ref "X1") (pin "7") (pinfunction "7_7") (pintype "bidirectional"))
    )
    (net (code "81") (name "/SYS.RESET#") (class "Default")
      (node (ref "BB.CAPE1") (pin "B9.10") (pinfunction "SYS.RESET#_B9.10") (pintype "bidirectional"))
      (node (ref "BB.CAPE1") (pin "T9.10") (pinfunction "SYS.RESET#_T9.10") (pintype "bidirectional"))
      (node (ref "X1") (pin "2") (pinfunction "2_2") (pintype "bidirectional"))
    )
    (net (code "82") (name "/SYS.VOUT") (class "Default")
      (node (ref "BB.CAPE1") (pin "B9.7") (pinfunction "SYS.5V(1)_B9.7") (pintype "bidirectional"))
      (node (ref "BB.CAPE1") (pin "B9.8") (pinfunction "SYS.5V(2)_B9.8") (pintype "bidirectional"))
      (node (ref "BB.CAPE1") (pin "T9.7") (pinfunction "SYS.5V(1)_T9.7") (pintype "bidirectional"))
      (node (ref "BB.CAPE1") (pin "T9.8") (pinfunction "SYS.5V(2)_T9.8") (pintype "bidirectional"))
      (node (ref "X1") (pin "4") (pinfunction "4_4") (pintype "bidirectional"))
    )
    (net (code "83") (name "/VIN.K") (class "Default")
      (node (ref "D1") (pin "K") (pinfunction "K_K") (pintype "bidirectional"))
      (node (ref "IC2") (pin "2") (pinfunction "IN_2") (pintype "bidirectional"))
    )
    (net (code "84") (name "GND") (class "Default")
      (node (ref "3V3") (pin "K") (pinfunction "K_K") (pintype "passive"))
      (node (ref "5V") (pin "K") (pinfunction "K_K") (pintype "passive"))
      (node (ref "BB.CAPE1") (pin "B8.1") (pinfunction "DGND1_B8.1") (pintype "bidirectional"))
      (node (ref "BB.CAPE1") (pin "B8.2") (pinfunction "DGND2_B8.2") (pintype "bidirectional"))
      (node (ref "BB.CAPE1") (pin "B9.1") (pinfunction "DGND1_B9.1") (pintype "bidirectional"))
      (node (ref "BB.CAPE1") (pin "B9.2") (pinfunction "DGND2_B9.2") (pintype "bidirectional"))
      (node (ref "BB.CAPE1") (pin "B9.43") (pinfunction "DGND3_B9.43") (pintype "bidirectional"))
      (node (ref "BB.CAPE1") (pin "B9.44") (pinfunction "DGND4_B9.44") (pintype "bidirectional"))
      (node (ref "BB.CAPE1") (pin "B9.45") (pinfunction "DGND5_B9.45") (pintype "bidirectional"))
      (node (ref "BB.CAPE1") (pin "B9.46") (pinfunction "DGND6_B9.46") (pintype "bidirectional"))
      (node (ref "BB.CAPE1") (pin "T8.1") (pinfunction "DGND1_T8.1") (pintype "bidirectional"))
      (node (ref "BB.CAPE1") (pin "T8.2") (pinfunction "DGND2_T8.2") (pintype "bidirectional"))
      (node (ref "BB.CAPE1") (pin "T9.1") (pinfunction "DGND1_T9.1") (pintype "bidirectional"))
      (node (ref "BB.CAPE1") (pin "T9.2") (pinfunction "DGND2_T9.2") (pintype "bidirectional"))
      (node (ref "BB.CAPE1") (pin "T9.43") (pinfunction "DGND3_T9.43") (pintype "bidirectional"))
      (node (ref "BB.CAPE1") (pin "T9.44") (pinfunction "DGND4_T9.44") (pintype "bidirectional"))
      (node (ref "BB.CAPE1") (pin "T9.45") (pinfunction "DGND5_T9.45") (pintype "bidirectional"))
      (node (ref "BB.CAPE1") (pin "T9.46") (pinfunction "DGND6_T9.46") (pintype "bidirectional"))
      (node (ref "C1") (pin "-") (pinfunction "-_-") (pintype "passive"))
      (node (ref "C2") (pin "-") (pinfunction "-_-") (pintype "passive"))
      (node (ref "C3") (pin "-") (pinfunction "-_-") (pintype "passive"))
      (node (ref "D2") (pin "A") (pinfunction "A_A") (pintype "bidirectional"))
      (node (ref "IC1") (pin "1") (pinfunction "GND_1") (pintype "bidirectional"))
      (node (ref "IC2") (pin "5") (pinfunction "GND1_5") (pintype "bidirectional"))
      (node (ref "IC2") (pin "6") (pinfunction "GND2_6") (pintype "bidirectional"))
      (node (ref "IC2") (pin "7") (pinfunction "GND3_7") (pintype "bidirectional"))
      (node (ref "IC2") (pin "8") (pinfunction "GND4_8") (pintype "bidirectional"))
      (node (ref "R1") (pin "2") (pinfunction "2_2") (pintype "bidirectional"))
      (node (ref "X1") (pin "1") (pinfunction "1_1") (pintype "bidirectional"))
      (node (ref "X1") (pin "10") (pinfunction "10_10") (pintype "bidirectional"))
    )
    (net (code "85") (name "Net-(3V3-PadA)") (class "Default")
      (node (ref "3V3") (pin "A") (pinfunction "A_A") (pintype "passive"))
      (node (ref "R3") (pin "2") (pinfunction "2_2") (pintype "bidirectional"))
    )
    (net (code "86") (name "Net-(5V-PadA)") (class "Default")
      (node (ref "5V") (pin "A") (pinfunction "A_A") (pintype "passive"))
      (node (ref "R2") (pin "2") (pinfunction "2_2") (pintype "bidirectional"))
    )
    (net (code "87") (name "Net-(IC2-FB)") (class "Default")
      (node (ref "C2") (pin "+") (pinfunction "+_+") (pintype "passive"))
      (node (ref "D3") (pin "A") (pinfunction "A_A") (pintype "bidirectional"))
      (node (ref "IC2") (pin "4") (pinfunction "FB_4") (pintype "bidirectional"))
      (node (ref "L1") (pin "2") (pinfunction "2_2") (pintype "bidirectional"))
    )
    (net (code "88") (name "Net-(IC2-SW)") (class "Default")
      (node (ref "D2") (pin "K") (pinfunction "K_K") (pintype "bidirectional"))
      (node (ref "IC2") (pin "3") (pinfunction "SW_3") (pintype "bidirectional"))
      (node (ref "L1") (pin "1") (pinfunction "1_1") (pintype "bidirectional"))
    )
    (net (code "89") (name "VCC") (class "Default")
      (node (ref "BB.CAPE1") (pin "B9.3") (pinfunction "VDD.3V3(1)_B9.3") (pintype "bidirectional"))
      (node (ref "BB.CAPE1") (pin "B9.4") (pinfunction "VDD.3V3(2)_B9.4") (pintype "bidirectional"))
      (node (ref "BB.CAPE1") (pin "T9.3") (pinfunction "VDD.3V3(1)_T9.3") (pintype "bidirectional"))
      (node (ref "BB.CAPE1") (pin "T9.4") (pinfunction "VDD.3V3(2)_T9.4") (pintype "bidirectional"))
      (node (ref "X1") (pin "5") (pinfunction "5_5") (pintype "bidirectional"))
    )
    (net (code "90") (name "VIN") (class "Default")
      (node (ref "C1") (pin "+") (pinfunction "+_+") (pintype "passive"))
      (node (ref "D1") (pin "A") (pinfunction "A_A") (pintype "bidirectional"))
      (node (ref "X1") (pin "9") (pinfunction "9_9") (pintype "bidirectional"))
    )
    (net (code "91") (name "unconnected-(FUD1-PadP$1)") (class "Default")
      (node (ref "FUD1") (pin "P$1") (pinfunction "P$1_P$1") (pintype "no_connect"))
    )
    (net (code "92") (name "unconnected-(FUD2-PadP$1)") (class "Default")
      (node (ref "FUD2") (pin "P$1") (pinfunction "P$1_P$1") (pintype "no_connect"))
    )
    (net (code "93") (name "unconnected-(FUD3-PadP$1)") (class "Default")
      (node (ref "FUD3") (pin "P$1") (pinfunction "P$1_P$1") (pintype "no_connect"))
    )
    (net (code "94") (name "unconnected-(FUD4-PadP$1)") (class "Default")
      (node (ref "FUD4") (pin "P$1") (pinfunction "P$1_P$1") (pintype "no_connect"))
    )
    (net (code "95") (name "unconnected-(FUD5-PadP$1)") (class "Default")
      (node (ref "FUD5") (pin "P$1") (pinfunction "P$1_P$1") (pintype "no_connect"))
    )
    (net (code "96") (name "unconnected-(FUD6-PadP$1)") (class "Default")
      (node (ref "FUD6") (pin "P$1") (pinfunction "P$1_P$1") (pintype "no_connect"))
    )
  )
)
